# DualLEDPanel_v1.net
KiCad netlist of a schematic drawn in EAGLE
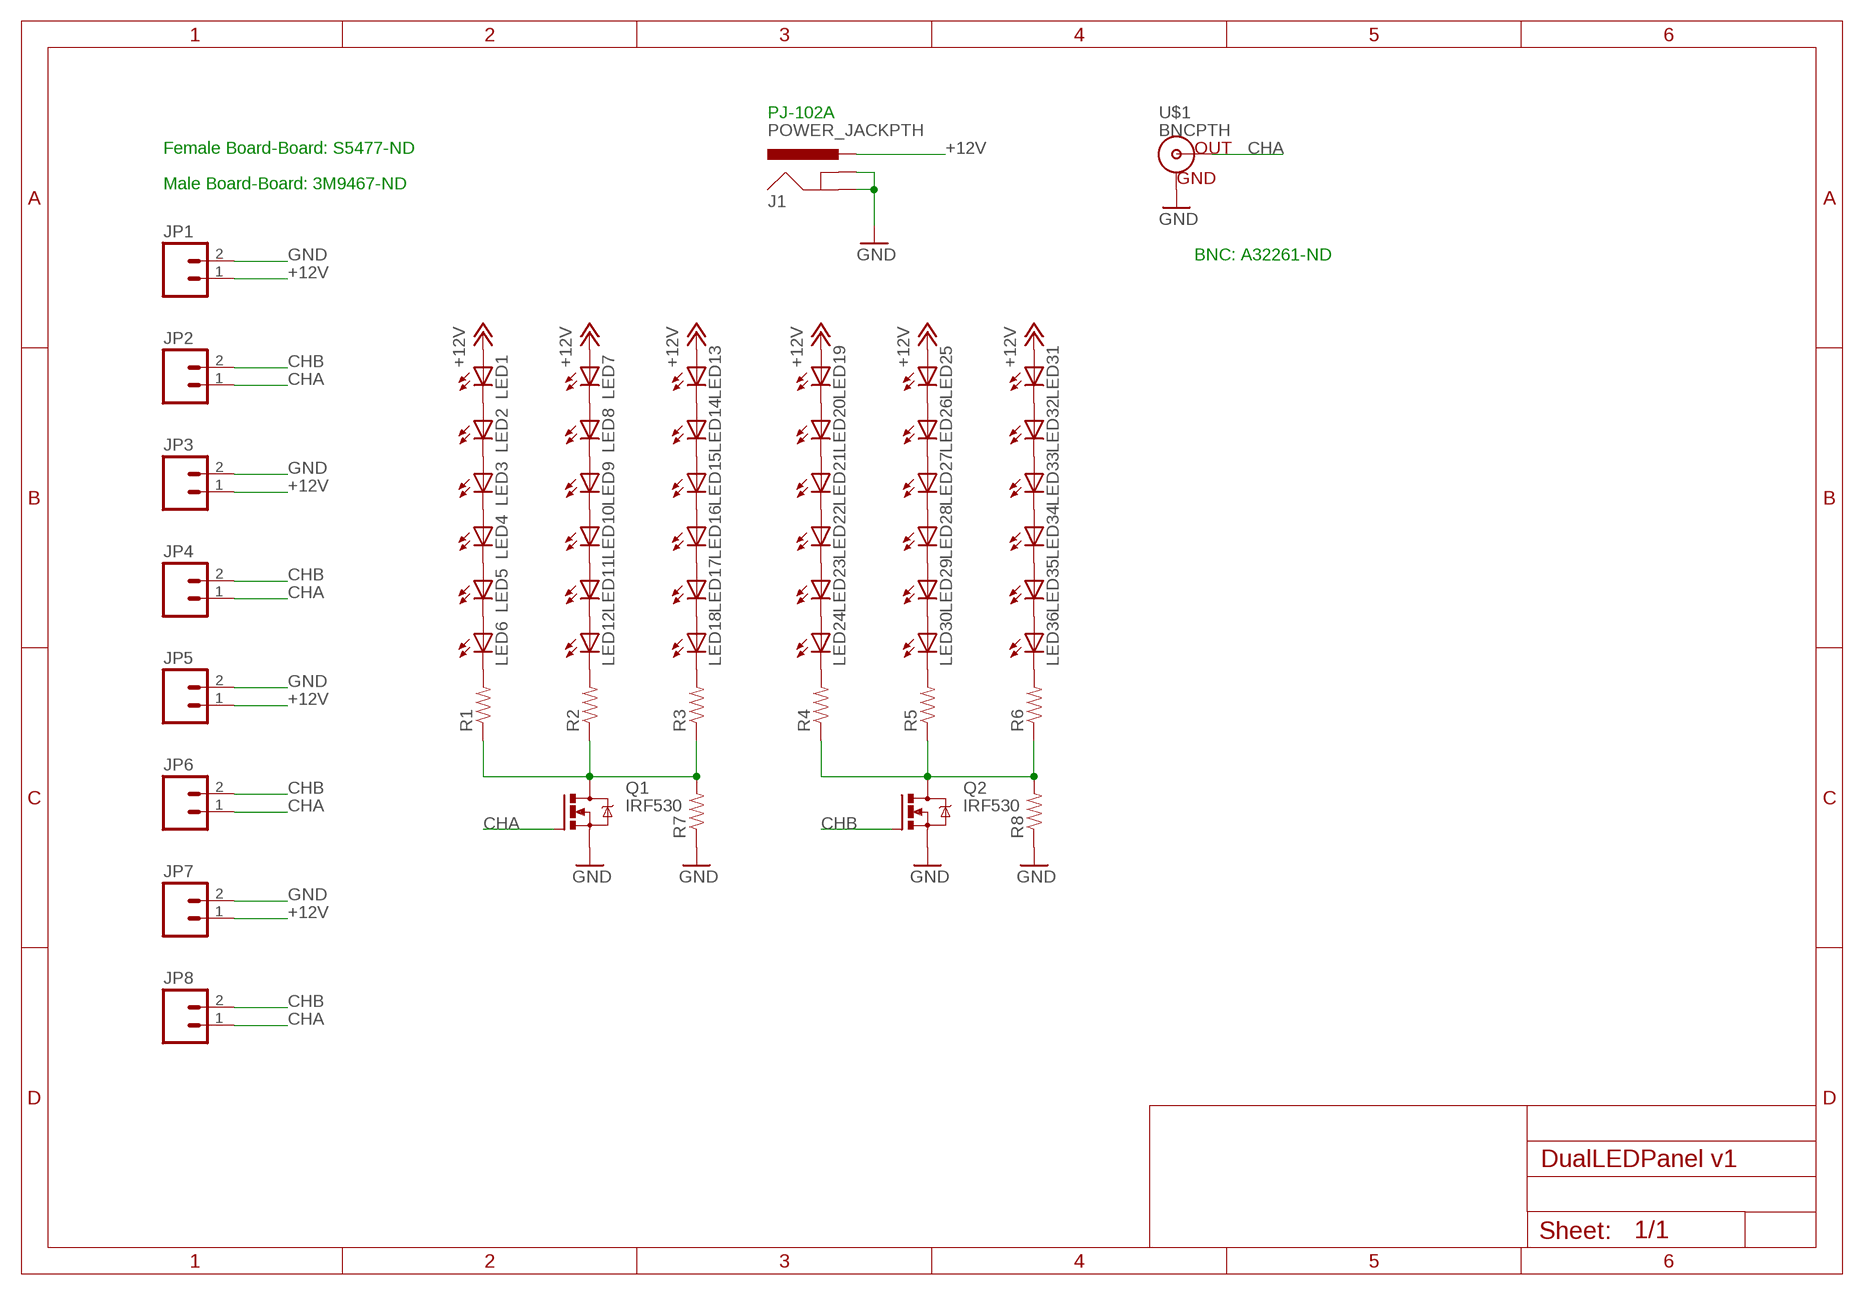
[diagram p0: schematic, sheet 1]

(export (version "E")
  (design (tool "Eeschema 10.0.6"))
  (components
    (comp (ref "J1")
      (value "POWER_JACKPTH")
      (footprint "eagle-import:POWER_JACK_PTH")
      (libsource (lib "eagle-import") (part "POWER_JACKPTH"))
    )
    (comp (ref "JP1")
      (value "M02PTH")
      (footprint "eagle-import:1X02")
      (libsource (lib "eagle-import") (part "M02PTH"))
    )
    (comp (ref "JP2")
      (value "M02PTH")
      (footprint "eagle-import:1X02")
      (libsource (lib "eagle-import") (part "M02PTH"))
    )
    (comp (ref "JP3")
      (value "M02PTH")
      (footprint "eagle-import:1X02")
      (libsource (lib "eagle-import") (part "M02PTH"))
    )
    (comp (ref "JP4")
      (value "M02PTH")
      (footprint "eagle-import:1X02")
      (libsource (lib "eagle-import") (part "M02PTH"))
    )
    (comp (ref "JP5")
      (value "M02PTH")
      (footprint "eagle-import:1X02")
      (libsource (lib "eagle-import") (part "M02PTH"))
    )
    (comp (ref "JP6")
      (value "M02PTH")
      (footprint "eagle-import:1X02")
      (libsource (lib "eagle-import") (part "M02PTH"))
    )
    (comp (ref "JP7")
      (value "M02PTH")
      (footprint "eagle-import:1X02")
      (libsource (lib "eagle-import") (part "M02PTH"))
    )
    (comp (ref "JP8")
      (value "M02PTH")
      (footprint "eagle-import:1X02")
      (libsource (lib "eagle-import") (part "M02PTH"))
    )
    (comp (ref "LED1")
      (value "LED5MM")
      (footprint "eagle-import:LED5MM")
      (libsource (lib "eagle-import") (part "LED5MM"))
    )
    (comp (ref "LED2")
      (value "LED5MM")
      (footprint "eagle-import:LED5MM")
      (libsource (lib "eagle-import") (part "LED5MM"))
    )
    (comp (ref "LED3")
      (value "LED5MM")
      (footprint "eagle-import:LED5MM")
      (libsource (lib "eagle-import") (part "LED5MM"))
    )
    (comp (ref "LED4")
      (value "LED5MM")
      (footprint "eagle-import:LED5MM")
      (libsource (lib "eagle-import") (part "LED5MM"))
    )
    (comp (ref "LED5")
      (value "LED5MM")
      (footprint "eagle-import:LED5MM")
      (libsource (lib "eagle-import") (part "LED5MM"))
    )
    (comp (ref "LED6")
      (value "LED5MM")
      (footprint "eagle-import:LED5MM")
      (libsource (lib "eagle-import") (part "LED5MM"))
    )
    (comp (ref "LED7")
      (value "LED5MM")
      (footprint "eagle-import:LED5MM")
      (libsource (lib "eagle-import") (part "LED5MM"))
    )
    (comp (ref "LED8")
      (value "LED5MM")
      (footprint "eagle-import:LED5MM")
      (libsource (lib "eagle-import") (part "LED5MM"))
    )
    (comp (ref "LED9")
      (value "LED5MM")
      (footprint "eagle-import:LED5MM")
      (libsource (lib "eagle-import") (part "LED5MM"))
    )
    (comp (ref "LED10")
      (value "LED5MM")
      (footprint "eagle-import:LED5MM")
      (libsource (lib "eagle-import") (part "LED5MM"))
    )
    (comp (ref "LED11")
      (value "LED5MM")
      (footprint "eagle-import:LED5MM")
      (libsource (lib "eagle-import") (part "LED5MM"))
    )
    (comp (ref "LED12")
      (value "LED5MM")
      (footprint "eagle-import:LED5MM")
      (libsource (lib "eagle-import") (part "LED5MM"))
    )
    (comp (ref "LED13")
      (value "LED5MM")
      (footprint "eagle-import:LED5MM")
      (libsource (lib "eagle-import") (part "LED5MM"))
    )
    (comp (ref "LED14")
      (value "LED5MM")
      (footprint "eagle-import:LED5MM")
      (libsource (lib "eagle-import") (part "LED5MM"))
    )
    (comp (ref "LED15")
      (value "LED5MM")
      (footprint "eagle-import:LED5MM")
      (libsource (lib "eagle-import") (part "LED5MM"))
    )
    (comp (ref "LED16")
      (value "LED5MM")
      (footprint "eagle-import:LED5MM")
      (libsource (lib "eagle-import") (part "LED5MM"))
    )
    (comp (ref "LED17")
      (value "LED5MM")
      (footprint "eagle-import:LED5MM")
      (libsource (lib "eagle-import") (part "LED5MM"))
    )
    (comp (ref "LED18")
      (value "LED5MM")
      (footprint "eagle-import:LED5MM")
      (libsource (lib "eagle-import") (part "LED5MM"))
    )
    (comp (ref "LED19")
      (value "LED5MM")
      (footprint "eagle-import:LED5MM")
      (libsource (lib "eagle-import") (part "LED5MM"))
    )
    (comp (ref "LED20")
      (value "LED5MM")
      (footprint "eagle-import:LED5MM")
      (libsource (lib "eagle-import") (part "LED5MM"))
    )
    (comp (ref "LED21")
      (value "LED5MM")
      (footprint "eagle-import:LED5MM")
      (libsource (lib "eagle-import") (part "LED5MM"))
    )
    (comp (ref "LED22")
      (value "LED5MM")
      (footprint "eagle-import:LED5MM")
      (libsource (lib "eagle-import") (part "LED5MM"))
    )
    (comp (ref "LED23")
      (value "LED5MM")
      (footprint "eagle-import:LED5MM")
      (libsource (lib "eagle-import") (part "LED5MM"))
    )
    (comp (ref "LED24")
      (value "LED5MM")
      (footprint "eagle-import:LED5MM")
      (libsource (lib "eagle-import") (part "LED5MM"))
    )
    (comp (ref "LED25")
      (value "LED5MM")
      (footprint "eagle-import:LED5MM")
      (libsource (lib "eagle-import") (part "LED5MM"))
    )
    (comp (ref "LED26")
      (value "LED5MM")
      (footprint "eagle-import:LED5MM")
      (libsource (lib "eagle-import") (part "LED5MM"))
    )
    (comp (ref "LED27")
      (value "LED5MM")
      (footprint "eagle-import:LED5MM")
      (libsource (lib "eagle-import") (part "LED5MM"))
    )
    (comp (ref "LED28")
      (value "LED5MM")
      (footprint "eagle-import:LED5MM")
      (libsource (lib "eagle-import") (part "LED5MM"))
    )
    (comp (ref "LED29")
      (value "LED5MM")
      (footprint "eagle-import:LED5MM")
      (libsource (lib "eagle-import") (part "LED5MM"))
    )
    (comp (ref "LED30")
      (value "LED5MM")
      (footprint "eagle-import:LED5MM")
      (libsource (lib "eagle-import") (part "LED5MM"))
    )
    (comp (ref "LED31")
      (value "LED5MM")
      (footprint "eagle-import:LED5MM")
      (libsource (lib "eagle-import") (part "LED5MM"))
    )
    (comp (ref "LED32")
      (value "LED5MM")
      (footprint "eagle-import:LED5MM")
      (libsource (lib "eagle-import") (part "LED5MM"))
    )
    (comp (ref "LED33")
      (value "LED5MM")
      (footprint "eagle-import:LED5MM")
      (libsource (lib "eagle-import") (part "LED5MM"))
    )
    (comp (ref "LED34")
      (value "LED5MM")
      (footprint "eagle-import:LED5MM")
      (libsource (lib "eagle-import") (part "LED5MM"))
    )
    (comp (ref "LED35")
      (value "LED5MM")
      (footprint "eagle-import:LED5MM")
      (libsource (lib "eagle-import") (part "LED5MM"))
    )
    (comp (ref "LED36")
      (value "LED5MM")
      (footprint "eagle-import:LED5MM")
      (libsource (lib "eagle-import") (part "LED5MM"))
    )
    (comp (ref "Q1")
      (value "IRF530")
      (footprint "eagle-import:TO220BV")
      (libsource (lib "eagle-import") (part "IRF530"))
    )
    (comp (ref "Q2")
      (value "IRF530")
      (footprint "eagle-import:TO220BV")
      (libsource (lib "eagle-import") (part "IRF530"))
    )
    (comp (ref "R1")
      (value "RESISTORPTH-1/4W")
      (footprint "eagle-import:AXIAL-0.4")
      (libsource (lib "eagle-import") (part "RESISTORPTH-1/4W"))
    )
    (comp (ref "R2")
      (value "RESISTORPTH-1/4W")
      (footprint "eagle-import:AXIAL-0.4")
      (libsource (lib "eagle-import") (part "RESISTORPTH-1/4W"))
    )
    (comp (ref "R3")
      (value "RESISTORPTH-1/4W")
      (footprint "eagle-import:AXIAL-0.4")
      (libsource (lib "eagle-import") (part "RESISTORPTH-1/4W"))
    )
    (comp (ref "R4")
      (value "RESISTORPTH-1/4W")
      (footprint "eagle-import:AXIAL-0.4")
      (libsource (lib "eagle-import") (part "RESISTORPTH-1/4W"))
    )
    (comp (ref "R5")
      (value "RESISTORPTH-1/4W")
      (footprint "eagle-import:AXIAL-0.4")
      (libsource (lib "eagle-import") (part "RESISTORPTH-1/4W"))
    )
    (comp (ref "R6")
      (value "RESISTORPTH-1/4W")
      (footprint "eagle-import:AXIAL-0.4")
      (libsource (lib "eagle-import") (part "RESISTORPTH-1/4W"))
    )
    (comp (ref "R7")
      (value "RESISTORPTH-1/4W")
      (footprint "eagle-import:AXIAL-0.4")
      (libsource (lib "eagle-import") (part "RESISTORPTH-1/4W"))
    )
    (comp (ref "R8")
      (value "RESISTORPTH-1/4W")
      (footprint "eagle-import:AXIAL-0.4")
      (libsource (lib "eagle-import") (part "RESISTORPTH-1/4W"))
    )
    (comp (ref "U$1")
      (value "BNCPTH")
      (footprint "eagle-import:BNC")
      (libsource (lib "eagle-import") (part "BNCPTH"))
    )
  )
  (nets
    (net (code "1") (name "+12V") (class "Default")
      (node (ref "J1") (pin "PWR") (pinfunction "PWR_PWR") (pintype "bidirectional"))
      (node (ref "JP1") (pin "1") (pinfunction "1_1") (pintype "passive"))
      (node (ref "JP3") (pin "1") (pinfunction "1_1") (pintype "passive"))
      (node (ref "JP5") (pin "1") (pinfunction "1_1") (pintype "passive"))
      (node (ref "JP7") (pin "1") (pinfunction "1_1") (pintype "passive"))
      (node (ref "LED1") (pin "A") (pinfunction "A_A") (pintype "passive"))
      (node (ref "LED13") (pin "A") (pinfunction "A_A") (pintype "passive"))
      (node (ref "LED19") (pin "A") (pinfunction "A_A") (pintype "passive"))
      (node (ref "LED25") (pin "A") (pinfunction "A_A") (pintype "passive"))
      (node (ref "LED31") (pin "A") (pinfunction "A_A") (pintype "passive"))
      (node (ref "LED7") (pin "A") (pinfunction "A_A") (pintype "passive"))
    )
    (net (code "2") (name "/CHA") (class "Default")
      (node (ref "JP2") (pin "1") (pinfunction "1_1") (pintype "passive"))
      (node (ref "JP4") (pin "1") (pinfunction "1_1") (pintype "passive"))
      (node (ref "JP6") (pin "1") (pinfunction "1_1") (pintype "passive"))
      (node (ref "JP8") (pin "1") (pinfunction "1_1") (pintype "passive"))
      (node (ref "Q1") (pin "G") (pinfunction "G_G") (pintype "passive"))
      (node (ref "U$1") (pin "S") (pinfunction "OUT_S") (pintype "bidirectional"))
    )
    (net (code "3") (name "/CHB") (class "Default")
      (node (ref "JP2") (pin "2") (pinfunction "2_2") (pintype "passive"))
      (node (ref "JP4") (pin "2") (pinfunction "2_2") (pintype "passive"))
      (node (ref "JP6") (pin "2") (pinfunction "2_2") (pintype "passive"))
      (node (ref "JP8") (pin "2") (pinfunction "2_2") (pintype "passive"))
      (node (ref "Q2") (pin "G") (pinfunction "G_G") (pintype "passive"))
    )
    (net (code "4") (name "GND") (class "Default")
      (node (ref "J1") (pin "GND") (pinfunction "GND_GND") (pintype "bidirectional"))
      (node (ref "J1") (pin "GNDBREAK") (pinfunction "GNDBREAK_GNDBREAK") (pintype "bidirectional"))
      (node (ref "JP1") (pin "2") (pinfunction "2_2") (pintype "passive"))
      (node (ref "JP3") (pin "2") (pinfunction "2_2") (pintype "passive"))
      (node (ref "JP5") (pin "2") (pinfunction "2_2") (pintype "passive"))
      (node (ref "JP7") (pin "2") (pinfunction "2_2") (pintype "passive"))
      (node (ref "Q1") (pin "S") (pinfunction "S_S") (pintype "passive"))
      (node (ref "Q2") (pin "S") (pinfunction "S_S") (pintype "passive"))
      (node (ref "R7") (pin "P$1") (pinfunction "1_P$1") (pintype "passive"))
      (node (ref "R8") (pin "P$1") (pinfunction "1_P$1") (pintype "passive"))
      (node (ref "U$1") (pin "GND") (pinfunction "GND_GND") (pintype "bidirectional"))
    )
    (net (code "5") (name "Net-(LED1-C)") (class "Default")
      (node (ref "LED1") (pin "K") (pinfunction "C_K") (pintype "passive"))
      (node (ref "LED2") (pin "A") (pinfunction "A_A") (pintype "passive"))
    )
    (net (code "6") (name "Net-(LED2-C)") (class "Default")
      (node (ref "LED2") (pin "K") (pinfunction "C_K") (pintype "passive"))
      (node (ref "LED3") (pin "A") (pinfunction "A_A") (pintype "passive"))
    )
    (net (code "7") (name "Net-(LED3-C)") (class "Default")
      (node (ref "LED3") (pin "K") (pinfunction "C_K") (pintype "passive"))
      (node (ref "LED4") (pin "A") (pinfunction "A_A") (pintype "passive"))
    )
    (net (code "8") (name "Net-(LED4-C)") (class "Default")
      (node (ref "LED4") (pin "K") (pinfunction "C_K") (pintype "passive"))
      (node (ref "LED5") (pin "A") (pinfunction "A_A") (pintype "passive"))
    )
    (net (code "9") (name "Net-(LED5-C)") (class "Default")
      (node (ref "LED5") (pin "K") (pinfunction "C_K") (pintype "passive"))
      (node (ref "LED6") (pin "A") (pinfunction "A_A") (pintype "passive"))
    )
    (net (code "10") (name "Net-(LED6-C)") (class "Default")
      (node (ref "LED6") (pin "K") (pinfunction "C_K") (pintype "passive"))
      (node (ref "R1") (pin "P$2") (pinfunction "2_P$2") (pintype "passive"))
    )
    (net (code "11") (name "Net-(LED7-C)") (class "Default")
      (node (ref "LED7") (pin "K") (pinfunction "C_K") (pintype "passive"))
      (node (ref "LED8") (pin "A") (pinfunction "A_A") (pintype "passive"))
    )
    (net (code "12") (name "Net-(LED8-C)") (class "Default")
      (node (ref "LED8") (pin "K") (pinfunction "C_K") (pintype "passive"))
      (node (ref "LED9") (pin "A") (pinfunction "A_A") (pintype "passive"))
    )
    (net (code "13") (name "Net-(LED9-C)") (class "Default")
      (node (ref "LED10") (pin "A") (pinfunction "A_A") (pintype "passive"))
      (node (ref "LED9") (pin "K") (pinfunction "C_K") (pintype "passive"))
    )
    (net (code "14") (name "Net-(LED10-C)") (class "Default")
      (node (ref "LED10") (pin "K") (pinfunction "C_K") (pintype "passive"))
      (node (ref "LED11") (pin "A") (pinfunction "A_A") (pintype "passive"))
    )
    (net (code "15") (name "Net-(LED11-C)") (class "Default")
      (node (ref "LED11") (pin "K") (pinfunction "C_K") (pintype "passive"))
      (node (ref "LED12") (pin "A") (pinfunction "A_A") (pintype "passive"))
    )
    (net (code "16") (name "Net-(LED12-C)") (class "Default")
      (node (ref "LED12") (pin "K") (pinfunction "C_K") (pintype "passive"))
      (node (ref "R2") (pin "P$2") (pinfunction "2_P$2") (pintype "passive"))
    )
    (net (code "17") (name "Net-(LED13-C)") (class "Default")
      (node (ref "LED13") (pin "K") (pinfunction "C_K") (pintype "passive"))
      (node (ref "LED14") (pin "A") (pinfunction "A_A") (pintype "passive"))
    )
    (net (code "18") (name "Net-(LED14-C)") (class "Default")
      (node (ref "LED14") (pin "K") (pinfunction "C_K") (pintype "passive"))
      (node (ref "LED15") (pin "A") (pinfunction "A_A") (pintype "passive"))
    )
    (net (code "19") (name "Net-(LED15-C)") (class "Default")
      (node (ref "LED15") (pin "K") (pinfunction "C_K") (pintype "passive"))
      (node (ref "LED16") (pin "A") (pinfunction "A_A") (pintype "passive"))
    )
    (net (code "20") (name "Net-(LED16-C)") (class "Default")
      (node (ref "LED16") (pin "K") (pinfunction "C_K") (pintype "passive"))
      (node (ref "LED17") (pin "A") (pinfunction "A_A") (pintype "passive"))
    )
    (net (code "21") (name "Net-(LED17-C)") (class "Default")
      (node (ref "LED17") (pin "K") (pinfunction "C_K") (pintype "passive"))
      (node (ref "LED18") (pin "A") (pinfunction "A_A") (pintype "passive"))
    )
    (net (code "22") (name "Net-(LED18-C)") (class "Default")
      (node (ref "LED18") (pin "K") (pinfunction "C_K") (pintype "passive"))
      (node (ref "R3") (pin "P$2") (pinfunction "2_P$2") (pintype "passive"))
    )
    (net (code "23") (name "Net-(LED19-C)") (class "Default")
      (node (ref "LED19") (pin "K") (pinfunction "C_K") (pintype "passive"))
      (node (ref "LED20") (pin "A") (pinfunction "A_A") (pintype "passive"))
    )
    (net (code "24") (name "Net-(LED20-C)") (class "Default")
      (node (ref "LED20") (pin "K") (pinfunction "C_K") (pintype "passive"))
      (node (ref "LED21") (pin "A") (pinfunction "A_A") (pintype "passive"))
    )
    (net (code "25") (name "Net-(LED21-C)") (class "Default")
      (node (ref "LED21") (pin "K") (pinfunction "C_K") (pintype "passive"))
      (node (ref "LED22") (pin "A") (pinfunction "A_A") (pintype "passive"))
    )
    (net (code "26") (name "Net-(LED22-C)") (class "Default")
      (node (ref "LED22") (pin "K") (pinfunction "C_K") (pintype "passive"))
      (node (ref "LED23") (pin "A") (pinfunction "A_A") (pintype "passive"))
    )
    (net (code "27") (name "Net-(LED23-C)") (class "Default")
      (node (ref "LED23") (pin "K") (pinfunction "C_K") (pintype "passive"))
      (node (ref "LED24") (pin "A") (pinfunction "A_A") (pintype "passive"))
    )
    (net (code "28") (name "Net-(LED24-C)") (class "Default")
      (node (ref "LED24") (pin "K") (pinfunction "C_K") (pintype "passive"))
      (node (ref "R4") (pin "P$2") (pinfunction "2_P$2") (pintype "passive"))
    )
    (net (code "29") (name "Net-(LED25-C)") (class "Default")
      (node (ref "LED25") (pin "K") (pinfunction "C_K") (pintype "passive"))
      (node (ref "LED26") (pin "A") (pinfunction "A_A") (pintype "passive"))
    )
    (net (code "30") (name "Net-(LED26-C)") (class "Default")
      (node (ref "LED26") (pin "K") (pinfunction "C_K") (pintype "passive"))
      (node (ref "LED27") (pin "A") (pinfunction "A_A") (pintype "passive"))
    )
    (net (code "31") (name "Net-(LED27-C)") (class "Default")
      (node (ref "LED27") (pin "K") (pinfunction "C_K") (pintype "passive"))
      (node (ref "LED28") (pin "A") (pinfunction "A_A") (pintype "passive"))
    )
    (net (code "32") (name "Net-(LED28-C)") (class "Default")
      (node (ref "LED28") (pin "K") (pinfunction "C_K") (pintype "passive"))
      (node (ref "LED29") (pin "A") (pinfunction "A_A") (pintype "passive"))
    )
    (net (code "33") (name "Net-(LED29-C)") (class "Default")
      (node (ref "LED29") (pin "K") (pinfunction "C_K") (pintype "passive"))
      (node (ref "LED30") (pin "A") (pinfunction "A_A") (pintype "passive"))
    )
    (net (code "34") (name "Net-(LED30-C)") (class "Default")
      (node (ref "LED30") (pin "K") (pinfunction "C_K") (pintype "passive"))
      (node (ref "R5") (pin "P$2") (pinfunction "2_P$2") (pintype "passive"))
    )
    (net (code "35") (name "Net-(LED31-C)") (class "Default")
      (node (ref "LED31") (pin "K") (pinfunction "C_K") (pintype "passive"))
      (node (ref "LED32") (pin "A") (pinfunction "A_A") (pintype "passive"))
    )
    (net (code "36") (name "Net-(LED32-C)") (class "Default")
      (node (ref "LED32") (pin "K") (pinfunction "C_K") (pintype "passive"))
      (node (ref "LED33") (pin "A") (pinfunction "A_A") (pintype "passive"))
    )
    (net (code "37") (name "Net-(LED33-C)") (class "Default")
      (node (ref "LED33") (pin "K") (pinfunction "C_K") (pintype "passive"))
      (node (ref "LED34") (pin "A") (pinfunction "A_A") (pintype "passive"))
    )
    (net (code "38") (name "Net-(LED34-C)") (class "Default")
      (node (ref "LED34") (pin "K") (pinfunction "C_K") (pintype "passive"))
      (node (ref "LED35") (pin "A") (pinfunction "A_A") (pintype "passive"))
    )
    (net (code "39") (name "Net-(LED35-C)") (class "Default")
      (node (ref "LED35") (pin "K") (pinfunction "C_K") (pintype "passive"))
      (node (ref "LED36") (pin "A") (pinfunction "A_A") (pintype "passive"))
    )
    (net (code "40") (name "Net-(LED36-C)") (class "Default")
      (node (ref "LED36") (pin "K") (pinfunction "C_K") (pintype "passive"))
      (node (ref "R6") (pin "P$2") (pinfunction "2_P$2") (pintype "passive"))
    )
    (net (code "41") (name "Net-(R1-1)") (class "Default")
      (node (ref "Q1") (pin "D") (pinfunction "D_D") (pintype "passive"))
      (node (ref "R1") (pin "P$1") (pinfunction "1_P$1") (pintype "passive"))
      (node (ref "R2") (pin "P$1") (pinfunction "1_P$1") (pintype "passive"))
      (node (ref "R3") (pin "P$1") (pinfunction "1_P$1") (pintype "passive"))
      (node (ref "R7") (pin "P$2") (pinfunction "2_P$2") (pintype "passive"))
    )
    (net (code "42") (name "Net-(R4-1)") (class "Default")
      (node (ref "Q2") (pin "D") (pinfunction "D_D") (pintype "passive"))
      (node (ref "R4") (pin "P$1") (pinfunction "1_P$1") (pintype "passive"))
      (node (ref "R5") (pin "P$1") (pinfunction "1_P$1") (pintype "passive"))
      (node (ref "R6") (pin "P$1") (pinfunction "1_P$1") (pintype "passive"))
      (node (ref "R8") (pin "P$2") (pinfunction "2_P$2") (pintype "passive"))
    )
  )
)
